# STM32Fx.net
KiCad netlist of a schematic drawn in Altium Designer
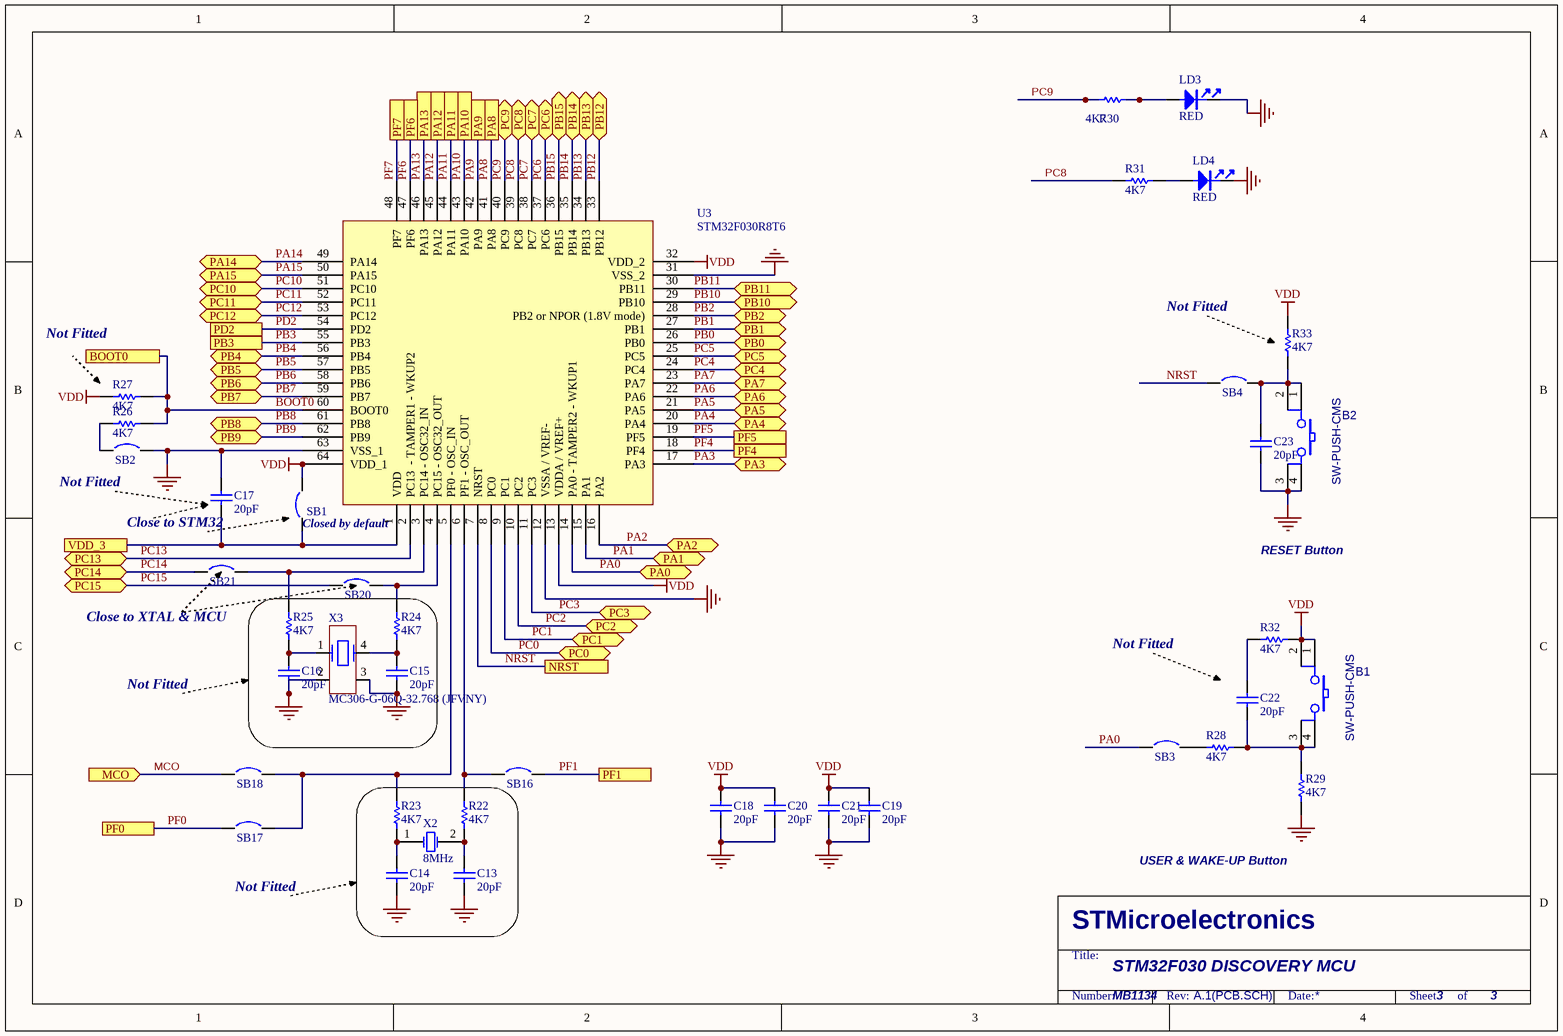
[diagram p0: STM32Fx.SchDoc]

(export (version "E")
  (design (tool "Eeschema 10.0.6"))
  (components
    (comp (ref "B1")
      (value "SW-PUSH-CMS")
      (footprint "SW_TL6120DF300QG")
      (description "Non-Open Push-Button 0.1A 24V")
      (libsource (lib "MB1134") (part "SW-PUSH-CMS"))
    )
    (comp (ref "B2")
      (value "SW-PUSH-CMS")
      (footprint "SW_TL6120DF300QG")
      (description "Non-Open Push-Button 0.1A 24V")
      (libsource (lib "MB1134") (part "SW-PUSH-CMS"))
    )
    (comp (ref "C13")
      (value "20pF")
      (footprint "CAPC1608X90")
      (description "Capacitor")
      (fields (field (name "PUBLISHER") "Altium Limited"))
      (libsource (lib "MB1134") (part "Cap"))
    )
    (comp (ref "C14")
      (value "20pF")
      (footprint "CAPC1608X90")
      (description "Capacitor")
      (fields (field (name "PUBLISHER") "Altium Limited"))
      (libsource (lib "MB1134") (part "Cap"))
    )
    (comp (ref "C15")
      (value "20pF")
      (footprint "CAPC1608X90")
      (description "Capacitor")
      (fields (field (name "PUBLISHER") "Altium Limited"))
      (libsource (lib "MB1134") (part "Cap"))
    )
    (comp (ref "C16")
      (value "20pF")
      (footprint "CAPC1608X90")
      (description "Capacitor")
      (fields (field (name "PUBLISHER") "Altium Limited"))
      (libsource (lib "MB1134") (part "Cap"))
    )
    (comp (ref "C17")
      (value "20pF")
      (footprint "CAPC1608X90")
      (description "Capacitor")
      (fields (field (name "PUBLISHER") "Altium Limited"))
      (libsource (lib "MB1134") (part "Cap"))
    )
    (comp (ref "C18")
      (value "20pF")
      (footprint "CAPC1608X90")
      (description "Capacitor")
      (fields (field (name "PUBLISHER") "Altium Limited"))
      (libsource (lib "MB1134") (part "Cap"))
    )
    (comp (ref "C19")
      (value "20pF")
      (footprint "CAPC1608X90")
      (description "Capacitor")
      (fields (field (name "PUBLISHER") "Altium Limited"))
      (libsource (lib "MB1134") (part "Cap"))
    )
    (comp (ref "C20")
      (value "20pF")
      (footprint "CAPC1608X90")
      (description "Capacitor")
      (fields (field (name "PUBLISHER") "Altium Limited"))
      (libsource (lib "MB1134") (part "Cap"))
    )
    (comp (ref "C21")
      (value "20pF")
      (footprint "CAPC1608X90")
      (description "Capacitor")
      (fields (field (name "PUBLISHER") "Altium Limited"))
      (libsource (lib "MB1134") (part "Cap"))
    )
    (comp (ref "C22")
      (value "20pF")
      (footprint "CAPC1608X90")
      (description "Capacitor")
      (fields (field (name "PUBLISHER") "Altium Limited"))
      (libsource (lib "MB1134") (part "Cap"))
    )
    (comp (ref "C23")
      (value "20pF")
      (footprint "CAPC1608X90")
      (description "Capacitor")
      (fields (field (name "PUBLISHER") "Altium Limited"))
      (libsource (lib "MB1134") (part "Cap"))
    )
    (comp (ref "LD3") (value "RED") (footprint "LED_SML-D12Y1WT86") (libsource (lib "MB1134") (part "PHOTO")))
    (comp (ref "LD4") (value "RED") (footprint "LED_SML-D12Y1WT86") (libsource (lib "MB1134") (part "PHOTO")))
    (comp (ref "R22")
      (value "4K7")
      (footprint "RESC1005X35N")
      (description "Resistor")
      (fields (field (name "PUBLISHER") "Altium Limited"))
      (libsource (lib "MB1134") (part "res1"))
    )
    (comp (ref "R23")
      (value "4K7")
      (footprint "RESC1005X35N")
      (description "Resistor")
      (fields (field (name "PUBLISHER") "Altium Limited"))
      (libsource (lib "MB1134") (part "res1"))
    )
    (comp (ref "R24")
      (value "4K7")
      (footprint "RESC1005X35N")
      (description "Resistor")
      (fields (field (name "PUBLISHER") "Altium Limited"))
      (libsource (lib "MB1134") (part "res1"))
    )
    (comp (ref "R25")
      (value "4K7")
      (footprint "RESC1005X35N")
      (description "Resistor")
      (fields (field (name "PUBLISHER") "Altium Limited"))
      (libsource (lib "MB1134") (part "res1"))
    )
    (comp (ref "R26")
      (value "4K7")
      (footprint "RESC1005X35N")
      (description "Resistor")
      (fields (field (name "PUBLISHER") "Altium Limited"))
      (libsource (lib "MB1134") (part "res1"))
    )
    (comp (ref "R27")
      (value "4K7")
      (footprint "RESC1005X35N")
      (description "Resistor")
      (fields (field (name "PUBLISHER") "Altium Limited"))
      (libsource (lib "MB1134") (part "res1"))
    )
    (comp (ref "R28")
      (value "4K7")
      (footprint "RESC1005X35N")
      (description "Resistor")
      (fields (field (name "PUBLISHER") "Altium Limited"))
      (libsource (lib "MB1134") (part "res1"))
    )
    (comp (ref "R29")
      (value "4K7")
      (footprint "RESC1005X35N")
      (description "Resistor")
      (fields (field (name "PUBLISHER") "Altium Limited"))
      (libsource (lib "MB1134") (part "res1"))
    )
    (comp (ref "R30")
      (value "4K7")
      (footprint "RESC1005X35N")
      (description "Resistor")
      (fields (field (name "PUBLISHER") "Altium Limited"))
      (libsource (lib "MB1134") (part "res1"))
    )
    (comp (ref "R31")
      (value "4K7")
      (footprint "RESC1005X35N")
      (description "Resistor")
      (fields (field (name "PUBLISHER") "Altium Limited"))
      (libsource (lib "MB1134") (part "res1"))
    )
    (comp (ref "R32")
      (value "4K7")
      (footprint "RESC1005X35N")
      (description "Resistor")
      (fields (field (name "PUBLISHER") "Altium Limited"))
      (libsource (lib "MB1134") (part "res1"))
    )
    (comp (ref "R33")
      (value "4K7")
      (footprint "RESC1005X35N")
      (description "Resistor")
      (fields (field (name "PUBLISHER") "Altium Limited"))
      (libsource (lib "MB1134") (part "res1"))
    )
    (comp (ref "SB1")
      (value "Circuit Breaker")
      (footprint "RESC1005X35N")
      (fields (field (name "PUBLISHER") "Altium Limited"))
      (libsource (lib "MB1134") (part "Circuit Breaker"))
    )
    (comp (ref "SB2")
      (value "Circuit Breaker")
      (footprint "RESC1005X35N")
      (fields (field (name "PUBLISHER") "Altium Limited"))
      (libsource (lib "MB1134") (part "Circuit Breaker"))
    )
    (comp (ref "SB3")
      (value "Circuit Breaker")
      (footprint "RESC1005X35N")
      (fields (field (name "PUBLISHER") "Altium Limited"))
      (libsource (lib "MB1134") (part "Circuit Breaker"))
    )
    (comp (ref "SB4")
      (value "Circuit Breaker")
      (footprint "RESC1005X35N")
      (fields (field (name "PUBLISHER") "Altium Limited"))
      (libsource (lib "MB1134") (part "Circuit Breaker"))
    )
    (comp (ref "SB16")
      (value "Circuit Breaker")
      (footprint "RESC1005X35N")
      (fields (field (name "PUBLISHER") "Altium Limited"))
      (libsource (lib "MB1134") (part "Circuit Breaker"))
    )
    (comp (ref "SB17")
      (value "Circuit Breaker")
      (footprint "RESC1005X35N")
      (fields (field (name "PUBLISHER") "Altium Limited"))
      (libsource (lib "MB1134") (part "Circuit Breaker"))
    )
    (comp (ref "SB18")
      (value "Circuit Breaker")
      (footprint "RESC1005X35N")
      (fields (field (name "PUBLISHER") "Altium Limited"))
      (libsource (lib "MB1134") (part "Circuit Breaker"))
    )
    (comp (ref "SB20")
      (value "Circuit Breaker")
      (footprint "RESC1005X35N")
      (fields (field (name "PUBLISHER") "Altium Limited"))
      (libsource (lib "MB1134") (part "Circuit Breaker"))
    )
    (comp (ref "SB21")
      (value "Circuit Breaker")
      (footprint "RESC1005X35N")
      (fields (field (name "PUBLISHER") "Altium Limited"))
      (libsource (lib "MB1134") (part "Circuit Breaker"))
    )
    (comp (ref "U3")
      (value "STM32F030R8T6")
      (footprint "QFP50P1200X1200X160-64N")
      (description "Advanced ARM based 32-bit Cortex M0 MCU with 64 Kbytes Flash and 8 Kbytes of SRAM")
      (libsource (lib "MB1134") (part "STM32F030R8T6"))
    )
    (comp (ref "X2")
      (value "8MHz")
      (footprint "XTAL_ECS-080-20-5PX-TR")
      (description "Crystal Oscillator")
      (fields (field (name "PUBLISHER") "Altium Limited"))
      (libsource (lib "MB1134") (part "XTAL"))
    )
    (comp (ref "X3")
      (value "MC306-G-06Q-32.768 (JFVNY)")
      (footprint "*XTAL_MC-306_32.7680K-A:_ROHS")
      (libsource (lib "MB1134") (part "MC306"))
    )
  )
  (nets
    (net (code "1") (name "/BOOT0") (class "Default")
      (node (ref "R26") (pin "2") (pinfunction "2_2") (pintype "passive"))
      (node (ref "R27") (pin "2") (pinfunction "2_2") (pintype "passive"))
      (node (ref "U3") (pin "60") (pinfunction "BOOT0_60") (pintype "passive"))
    )
    (net (code "2") (name "/MCO") (class "Default")
      (node (ref "SB18") (pin "1") (pinfunction "1_1") (pintype "passive"))
    )
    (net (code "3") (name "/NRST") (class "Default")
      (node (ref "SB4") (pin "1") (pinfunction "1_1") (pintype "passive"))
      (node (ref "U3") (pin "7") (pinfunction "NRST_7") (pintype "passive"))
    )
    (net (code "4") (name "/PA0") (class "Default")
      (node (ref "SB3") (pin "1") (pinfunction "1_1") (pintype "passive"))
      (node (ref "U3") (pin "14") (pinfunction "PA0_-_TAMPER2_-_WKUP1_14") (pintype "passive"))
    )
    (net (code "5") (name "/PA1") (class "Default")
      (node (ref "U3") (pin "15") (pinfunction "PA1_15") (pintype "passive"))
    )
    (net (code "6") (name "/PA2") (class "Default")
      (node (ref "U3") (pin "16") (pinfunction "PA2_16") (pintype "passive"))
    )
    (net (code "7") (name "/PA3") (class "Default")
      (node (ref "U3") (pin "17") (pinfunction "PA3_17") (pintype "passive"))
    )
    (net (code "8") (name "/PA4") (class "Default")
      (node (ref "U3") (pin "20") (pinfunction "PA4_20") (pintype "passive"))
    )
    (net (code "9") (name "/PA5") (class "Default")
      (node (ref "U3") (pin "21") (pinfunction "PA5_21") (pintype "passive"))
    )
    (net (code "10") (name "/PA6") (class "Default")
      (node (ref "U3") (pin "22") (pinfunction "PA6_22") (pintype "passive"))
    )
    (net (code "11") (name "/PA7") (class "Default")
      (node (ref "U3") (pin "23") (pinfunction "PA7_23") (pintype "passive"))
    )
    (net (code "12") (name "/PA8") (class "Default")
      (node (ref "U3") (pin "41") (pinfunction "PA8_41") (pintype "passive"))
    )
    (net (code "13") (name "/PA9") (class "Default")
      (node (ref "U3") (pin "42") (pinfunction "PA9_42") (pintype "passive"))
    )
    (net (code "14") (name "/PA10") (class "Default")
      (node (ref "U3") (pin "43") (pinfunction "PA10_43") (pintype "passive"))
    )
    (net (code "15") (name "/PA11") (class "Default")
      (node (ref "U3") (pin "44") (pinfunction "PA11_44") (pintype "passive"))
    )
    (net (code "16") (name "/PA12") (class "Default")
      (node (ref "U3") (pin "45") (pinfunction "PA12_45") (pintype "passive"))
    )
    (net (code "17") (name "/PA13") (class "Default")
      (node (ref "U3") (pin "46") (pinfunction "PA13_46") (pintype "passive"))
    )
    (net (code "18") (name "/PA14") (class "Default")
      (node (ref "U3") (pin "49") (pinfunction "PA14_49") (pintype "passive"))
    )
    (net (code "19") (name "/PA15") (class "Default")
      (node (ref "U3") (pin "50") (pinfunction "PA15_50") (pintype "passive"))
    )
    (net (code "20") (name "/PB0") (class "Default")
      (node (ref "U3") (pin "26") (pinfunction "PB0_26") (pintype "passive"))
    )
    (net (code "21") (name "/PB1") (class "Default")
      (node (ref "U3") (pin "27") (pinfunction "PB1_27") (pintype "passive"))
    )
    (net (code "22") (name "/PB2") (class "Default")
      (node (ref "U3") (pin "28") (pinfunction "PB2_or_NPOR_(1.8V_mode)_28") (pintype "passive"))
    )
    (net (code "23") (name "/PB3") (class "Default")
      (node (ref "U3") (pin "55") (pinfunction "PB3_55") (pintype "passive"))
    )
    (net (code "24") (name "/PB4") (class "Default")
      (node (ref "U3") (pin "56") (pinfunction "PB4_56") (pintype "passive"))
    )
    (net (code "25") (name "/PB5") (class "Default")
      (node (ref "U3") (pin "57") (pinfunction "PB5_57") (pintype "passive"))
    )
    (net (code "26") (name "/PB6") (class "Default")
      (node (ref "U3") (pin "58") (pinfunction "PB6_58") (pintype "passive"))
    )
    (net (code "27") (name "/PB7") (class "Default")
      (node (ref "U3") (pin "59") (pinfunction "PB7_59") (pintype "passive"))
    )
    (net (code "28") (name "/PB8") (class "Default")
      (node (ref "U3") (pin "61") (pinfunction "PB8_61") (pintype "passive"))
    )
    (net (code "29") (name "/PB9") (class "Default")
      (node (ref "U3") (pin "62") (pinfunction "PB9_62") (pintype "passive"))
    )
    (net (code "30") (name "/PB10") (class "Default")
      (node (ref "U3") (pin "29") (pinfunction "PB10_29") (pintype "passive"))
    )
    (net (code "31") (name "/PB11") (class "Default")
      (node (ref "U3") (pin "30") (pinfunction "PB11_30") (pintype "passive"))
    )
    (net (code "32") (name "/PB12") (class "Default")
      (node (ref "U3") (pin "33") (pinfunction "PB12_33") (pintype "passive"))
    )
    (net (code "33") (name "/PB13") (class "Default")
      (node (ref "U3") (pin "34") (pinfunction "PB13_34") (pintype "passive"))
    )
    (net (code "34") (name "/PB14") (class "Default")
      (node (ref "U3") (pin "35") (pinfunction "PB14_35") (pintype "passive"))
    )
    (net (code "35") (name "/PB15") (class "Default")
      (node (ref "U3") (pin "36") (pinfunction "PB15_36") (pintype "passive"))
    )
    (net (code "36") (name "/PC0") (class "Default")
      (node (ref "U3") (pin "8") (pinfunction "PC0_8") (pintype "passive"))
    )
    (net (code "37") (name "/PC1") (class "Default")
      (node (ref "U3") (pin "9") (pinfunction "PC1_9") (pintype "passive"))
    )
    (net (code "38") (name "/PC2") (class "Default")
      (node (ref "U3") (pin "10") (pinfunction "PC2_10") (pintype "passive"))
    )
    (net (code "39") (name "/PC3") (class "Default")
      (node (ref "U3") (pin "11") (pinfunction "PC3_11") (pintype "passive"))
    )
    (net (code "40") (name "/PC4") (class "Default")
      (node (ref "U3") (pin "24") (pinfunction "PC4_24") (pintype "passive"))
    )
    (net (code "41") (name "/PC5") (class "Default")
      (node (ref "U3") (pin "25") (pinfunction "PC5_25") (pintype "passive"))
    )
    (net (code "42") (name "/PC6") (class "Default")
      (node (ref "U3") (pin "37") (pinfunction "PC6_37") (pintype "passive"))
    )
    (net (code "43") (name "/PC7") (class "Default")
      (node (ref "U3") (pin "38") (pinfunction "PC7_38") (pintype "passive"))
    )
    (net (code "44") (name "/PC8") (class "Default")
      (node (ref "R31") (pin "1") (pinfunction "1_1") (pintype "passive"))
      (node (ref "U3") (pin "39") (pinfunction "PC8_39") (pintype "passive"))
    )
    (net (code "45") (name "/PC9") (class "Default")
      (node (ref "R30") (pin "1") (pinfunction "1_1") (pintype "passive"))
      (node (ref "U3") (pin "40") (pinfunction "PC9_40") (pintype "passive"))
    )
    (net (code "46") (name "/PC10") (class "Default")
      (node (ref "U3") (pin "51") (pinfunction "PC10_51") (pintype "passive"))
    )
    (net (code "47") (name "/PC11") (class "Default")
      (node (ref "U3") (pin "52") (pinfunction "PC11_52") (pintype "passive"))
    )
    (net (code "48") (name "/PC12") (class "Default")
      (node (ref "U3") (pin "53") (pinfunction "PC12_53") (pintype "passive"))
    )
    (net (code "49") (name "/PC13") (class "Default")
      (node (ref "U3") (pin "2") (pinfunction "PC13__-_TAMPER1_-_WKUP2_2") (pintype "passive"))
    )
    (net (code "50") (name "/PC14") (class "Default")
      (node (ref "SB21") (pin "1") (pinfunction "1_1") (pintype "passive"))
    )
    (net (code "51") (name "/PC15") (class "Default")
      (node (ref "SB20") (pin "1") (pinfunction "1_1") (pintype "passive"))
    )
    (net (code "52") (name "/PD2") (class "Default")
      (node (ref "U3") (pin "54") (pinfunction "PD2_54") (pintype "passive"))
    )
    (net (code "53") (name "/PF0") (class "Default")
      (node (ref "SB17") (pin "1") (pinfunction "1_1") (pintype "passive"))
    )
    (net (code "54") (name "/PF1") (class "Default")
      (node (ref "SB16") (pin "2") (pinfunction "2_2") (pintype "passive"))
    )
    (net (code "55") (name "/PF4") (class "Default")
      (node (ref "U3") (pin "18") (pinfunction "PF4_18") (pintype "passive"))
    )
    (net (code "56") (name "/PF5") (class "Default")
      (node (ref "U3") (pin "19") (pinfunction "PF5_19") (pintype "passive"))
    )
    (net (code "57") (name "/PF6") (class "Default")
      (node (ref "U3") (pin "47") (pinfunction "PF6_47") (pintype "passive"))
    )
    (net (code "58") (name "/PF7") (class "Default")
      (node (ref "U3") (pin "48") (pinfunction "PF7_48") (pintype "passive"))
    )
    (net (code "59") (name "/VDD_3") (class "Default")
      (node (ref "C17") (pin "1") (pinfunction "1_1") (pintype "passive"))
      (node (ref "SB1") (pin "1") (pinfunction "1_1") (pintype "passive"))
      (node (ref "U3") (pin "1") (pinfunction "VDD_1") (pintype "passive"))
    )
    (net (code "60") (name "GND") (class "Default")
      (node (ref "B2") (pin "3") (pinfunction "3_3") (pintype "passive"))
      (node (ref "B2") (pin "4") (pinfunction "4_4") (pintype "passive"))
      (node (ref "C13") (pin "1") (pinfunction "1_1") (pintype "passive"))
      (node (ref "C14") (pin "1") (pinfunction "1_1") (pintype "passive"))
      (node (ref "C15") (pin "1") (pinfunction "1_1") (pintype "passive"))
      (node (ref "C16") (pin "1") (pinfunction "1_1") (pintype "passive"))
      (node (ref "C17") (pin "2") (pinfunction "2_2") (pintype "passive"))
      (node (ref "C18") (pin "1") (pinfunction "1_1") (pintype "passive"))
      (node (ref "C19") (pin "2") (pinfunction "2_2") (pintype "passive"))
      (node (ref "C20") (pin "2") (pinfunction "2_2") (pintype "passive"))
      (node (ref "C21") (pin "2") (pinfunction "2_2") (pintype "passive"))
      (node (ref "C23") (pin "1") (pinfunction "1_1") (pintype "passive"))
      (node (ref "LD3") (pin "2") (pintype "passive"))
      (node (ref "LD4") (pin "2") (pintype "passive"))
      (node (ref "R29") (pin "1") (pinfunction "1_1") (pintype "passive"))
      (node (ref "SB2") (pin "2") (pinfunction "2_2") (pintype "passive"))
      (node (ref "U3") (pin "12") (pinfunction "VSSA_/_VREF-_12") (pintype "passive"))
      (node (ref "U3") (pin "31") (pinfunction "VSS_2_31") (pintype "passive"))
      (node (ref "U3") (pin "63") (pinfunction "VSS_1_63") (pintype "passive"))
      (node (ref "X3") (pin "2") (pinfunction "2_2") (pintype "passive"))
      (node (ref "X3") (pin "3") (pinfunction "3_3") (pintype "passive"))
    )
    (net (code "61") (name "Net-(B1-Pad3)") (class "Default")
      (node (ref "B1") (pin "3") (pinfunction "3_3") (pintype "passive"))
      (node (ref "B1") (pin "4") (pinfunction "4_4") (pintype "passive"))
      (node (ref "C22") (pin "1") (pinfunction "1_1") (pintype "passive"))
      (node (ref "R28") (pin "2") (pinfunction "2_2") (pintype "passive"))
      (node (ref "R29") (pin "2") (pinfunction "2_2") (pintype "passive"))
    )
    (net (code "62") (name "Net-(B2-Pad1)") (class "Default")
      (node (ref "B2") (pin "1") (pinfunction "1_1") (pintype "passive"))
      (node (ref "B2") (pin "2") (pinfunction "2_2") (pintype "passive"))
      (node (ref "C23") (pin "2") (pinfunction "2_2") (pintype "passive"))
      (node (ref "R33") (pin "1") (pinfunction "1_1") (pintype "passive"))
      (node (ref "SB4") (pin "2") (pinfunction "2_2") (pintype "passive"))
    )
    (net (code "63") (name "Net-(C15-Pad2)") (class "Default")
      (node (ref "C15") (pin "2") (pinfunction "2_2") (pintype "passive"))
      (node (ref "R24") (pin "1") (pinfunction "1_1") (pintype "passive"))
      (node (ref "X3") (pin "4") (pinfunction "4_4") (pintype "passive"))
    )
    (net (code "64") (name "Net-(C16-Pad2)") (class "Default")
      (node (ref "C16") (pin "2") (pinfunction "2_2") (pintype "passive"))
      (node (ref "R25") (pin "1") (pinfunction "1_1") (pintype "passive"))
      (node (ref "X3") (pin "1") (pinfunction "1_1") (pintype "passive"))
    )
    (net (code "65") (name "Net-(C22-Pad2)") (class "Default")
      (node (ref "C22") (pin "2") (pinfunction "2_2") (pintype "passive"))
      (node (ref "R32") (pin "1") (pinfunction "1_1") (pintype "passive"))
    )
    (net (code "66") (name "Net-(LD3-Pad1)") (class "Default")
      (node (ref "LD3") (pin "1") (pintype "passive"))
      (node (ref "R30") (pin "2") (pinfunction "2_2") (pintype "passive"))
    )
    (net (code "67") (name "Net-(LD4-Pad1)") (class "Default")
      (node (ref "LD4") (pin "1") (pintype "passive"))
      (node (ref "R31") (pin "2") (pinfunction "2_2") (pintype "passive"))
    )
    (net (code "68") (name "Net-(R26-Pad1)") (class "Default")
      (node (ref "R26") (pin "1") (pinfunction "1_1") (pintype "passive"))
      (node (ref "SB2") (pin "1") (pinfunction "1_1") (pintype "passive"))
    )
    (net (code "69") (name "Net-(R28-Pad1)") (class "Default")
      (node (ref "R28") (pin "1") (pinfunction "1_1") (pintype "passive"))
      (node (ref "SB3") (pin "2") (pinfunction "2_2") (pintype "passive"))
    )
    (net (code "70") (name "Net-(U3-PC14_-_OSC32_IN)") (class "Default")
      (node (ref "R25") (pin "2") (pinfunction "2_2") (pintype "passive"))
      (node (ref "SB21") (pin "2") (pinfunction "2_2") (pintype "passive"))
      (node (ref "U3") (pin "3") (pinfunction "PC14_-_OSC32_IN_3") (pintype "passive"))
    )
    (net (code "71") (name "Net-(U3-PC15_-_OSC32_OUT)") (class "Default")
      (node (ref "R24") (pin "2") (pinfunction "2_2") (pintype "passive"))
      (node (ref "SB20") (pin "2") (pinfunction "2_2") (pintype "passive"))
      (node (ref "U3") (pin "4") (pinfunction "PC15_-_OSC32_OUT_4") (pintype "passive"))
    )
    (net (code "72") (name "Net-(U3-PF0_-_OSC_IN)") (class "Default")
      (node (ref "R23") (pin "2") (pinfunction "2_2") (pintype "passive"))
      (node (ref "SB17") (pin "2") (pinfunction "2_2") (pintype "passive"))
      (node (ref "SB18") (pin "2") (pinfunction "2_2") (pintype "passive"))
      (node (ref "U3") (pin "5") (pinfunction "PF0_-_OSC_IN_5") (pintype "passive"))
    )
    (net (code "73") (name "Net-(U3-PF1_-_OSC_OUT)") (class "Default")
      (node (ref "R22") (pin "1") (pinfunction "1_1") (pintype "passive"))
      (node (ref "SB16") (pin "1") (pinfunction "1_1") (pintype "passive"))
      (node (ref "U3") (pin "6") (pinfunction "PF1_-_OSC_OUT_6") (pintype "passive"))
    )
    (net (code "74") (name "Net-(X2-OSC1)") (class "Default")
      (node (ref "C14") (pin "2") (pinfunction "2_2") (pintype "passive"))
      (node (ref "R23") (pin "1") (pinfunction "1_1") (pintype "passive"))
      (node (ref "X2") (pin "1") (pinfunction "OSC1_1") (pintype "passive"))
    )
    (net (code "75") (name "Net-(X2-OSC2)") (class "Default")
      (node (ref "C13") (pin "2") (pinfunction "2_2") (pintype "passive"))
      (node (ref "R22") (pin "2") (pinfunction "2_2") (pintype "passive"))
      (node (ref "X2") (pin "2") (pinfunction "OSC2_2") (pintype "passive"))
    )
    (net (code "76") (name "VDD") (class "Default")
      (node (ref "B1") (pin "1") (pinfunction "1_1") (pintype "passive"))
      (node (ref "B1") (pin "2") (pinfunction "2_2") (pintype "passive"))
      (node (ref "C18") (pin "2") (pinfunction "2_2") (pintype "passive"))
      (node (ref "C19") (pin "1") (pinfunction "1_1") (pintype "passive"))
      (node (ref "C20") (pin "1") (pinfunction "1_1") (pintype "passive"))
      (node (ref "C21") (pin "1") (pinfunction "1_1") (pintype "passive"))
      (node (ref "R27") (pin "1") (pinfunction "1_1") (pintype "passive"))
      (node (ref "R32") (pin "2") (pinfunction "2_2") (pintype "passive"))
      (node (ref "R33") (pin "2") (pinfunction "2_2") (pintype "passive"))
      (node (ref "SB1") (pin "2") (pinfunction "2_2") (pintype "passive"))
      (node (ref "U3") (pin "13") (pinfunction "VDDA_/_VREF+_13") (pintype "passive"))
      (node (ref "U3") (pin "32") (pinfunction "VDD_2_32") (pintype "passive"))
      (node (ref "U3") (pin "64") (pinfunction "VDD_1_64") (pintype "passive"))
    )
  )
)
